# SX1308.net
KiCad netlist of a schematic drawn in Altium Designer
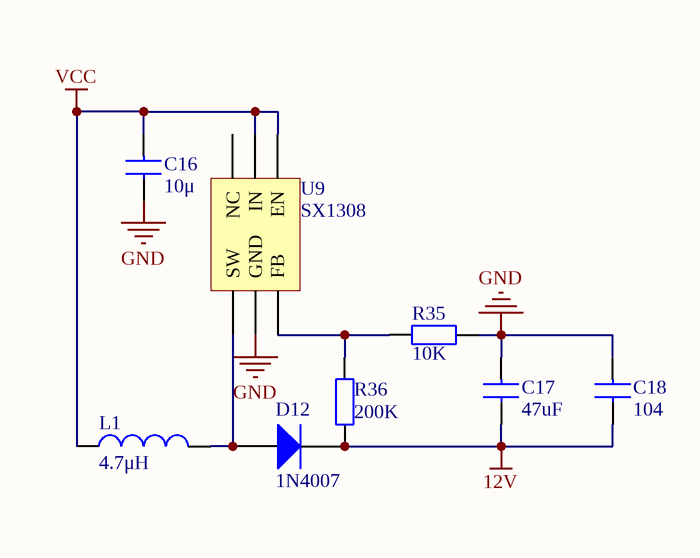
[diagram p0: SX1308升压电路.SchDoc]

(export (version "E")
  (design (tool "Eeschema 10.0.6"))
  (components
    (comp (ref "C16")
      (value "10μ")
      (footprint "mypcb:C0805")
      (description "Capacitor")
      (libsource (lib "MySchLib") (part "CAP（0805）"))
    )
    (comp (ref "C17")
      (value "47uF")
      (footprint "mypcb:R1206")
      (description "Capacitor")
      (libsource (lib "MySchLib") (part "CAP（0805）"))
    )
    (comp (ref "C18")
      (value "104")
      (footprint "mypcb:c0603")
      (description "Capacitor")
      (libsource (lib "MySchLib") (part "CAP（0805）"))
    )
    (comp (ref "D12")
      (value "1N4007")
      (footprint "mypcb:R0805")
      (description "1 Amp General Purpose Rectifier")
      (fields (field (name "PUBLISHER") "Altium Limited"))
      (libsource (lib "MySchLib") (part "1N4007"))
    )
    (comp (ref "L1")
      (value "4.7μH")
      (footprint "mypcb:CD43")
      (description "Inductor")
      (fields (field (name "PUBLISHER") "Altium Limited"))
      (libsource (lib "MySchLib") (part "Inductor"))
    )
    (comp (ref "R35")
      (value "10K")
      (footprint "R0603")
      (description "Resistor")
      (fields (field (name "Comment") "Res2") (field (name "PUBLISHER") "Altium Limited"))
      (libsource (lib "MySchLib") (part "Res2"))
    )
    (comp (ref "R36")
      (value "200K")
      (footprint "R0603")
      (description "Resistor")
      (fields (field (name "Comment") "Res2") (field (name "PUBLISHER") "Altium Limited"))
      (libsource (lib "") (part "Res2_1"))
    )
    (comp (ref "U9") (value "SX1308") (footprint "mypcb:SOT-26") (libsource (lib "MySchLib") (part "SX1308")))
  )
  (nets
    (net (code "1") (name "12V") (class "Default")
      (node (ref "C17") (pin "2") (pinfunction "2_2") (pintype "passive"))
      (node (ref "C18") (pin "2") (pinfunction "2_2") (pintype "passive"))
      (node (ref "D12") (pin "2") (pinfunction "K_2") (pintype "passive"))
      (node (ref "R36") (pin "2") (pinfunction "2_2") (pintype "passive"))
    )
    (net (code "2") (name "GND") (class "Default")
      (node (ref "C16") (pin "2") (pinfunction "2_2") (pintype "passive"))
      (node (ref "C17") (pin "1") (pinfunction "1_1") (pintype "passive"))
      (node (ref "C18") (pin "1") (pinfunction "1_1") (pintype "passive"))
      (node (ref "R35") (pin "2") (pinfunction "2_2") (pintype "passive"))
      (node (ref "U9") (pin "2") (pinfunction "GND_2") (pintype "passive"))
    )
    (net (code "3") (name "Net-(D12-A)") (class "Default")
      (node (ref "D12") (pin "1") (pinfunction "A_1") (pintype "passive"))
      (node (ref "L1") (pin "2") (pinfunction "2_2") (pintype "passive"))
      (node (ref "U9") (pin "1") (pinfunction "SW_1") (pintype "passive"))
    )
    (net (code "4") (name "Net-(U9-FB)") (class "Default")
      (node (ref "R35") (pin "1") (pinfunction "1_1") (pintype "passive"))
      (node (ref "R36") (pin "1") (pinfunction "1_1") (pintype "passive"))
      (node (ref "U9") (pin "3") (pinfunction "FB_3") (pintype "passive"))
    )
    (net (code "5") (name "VCC") (class "Default")
      (node (ref "C16") (pin "1") (pinfunction "1_1") (pintype "passive"))
      (node (ref "L1") (pin "1") (pinfunction "1_1") (pintype "passive"))
      (node (ref "U9") (pin "4") (pinfunction "EN_4") (pintype "passive"))
      (node (ref "U9") (pin "5") (pinfunction "IN_5") (pintype "passive"))
    )
    (net (code "6") (name "unconnected-(U9-NC-Pad6)") (class "Default")
      (node (ref "U9") (pin "6") (pinfunction "NC_6") (pintype "passive"))
    )
  )
)
